# uc.net
KiCad netlist of a schematic drawn in Altium Designer
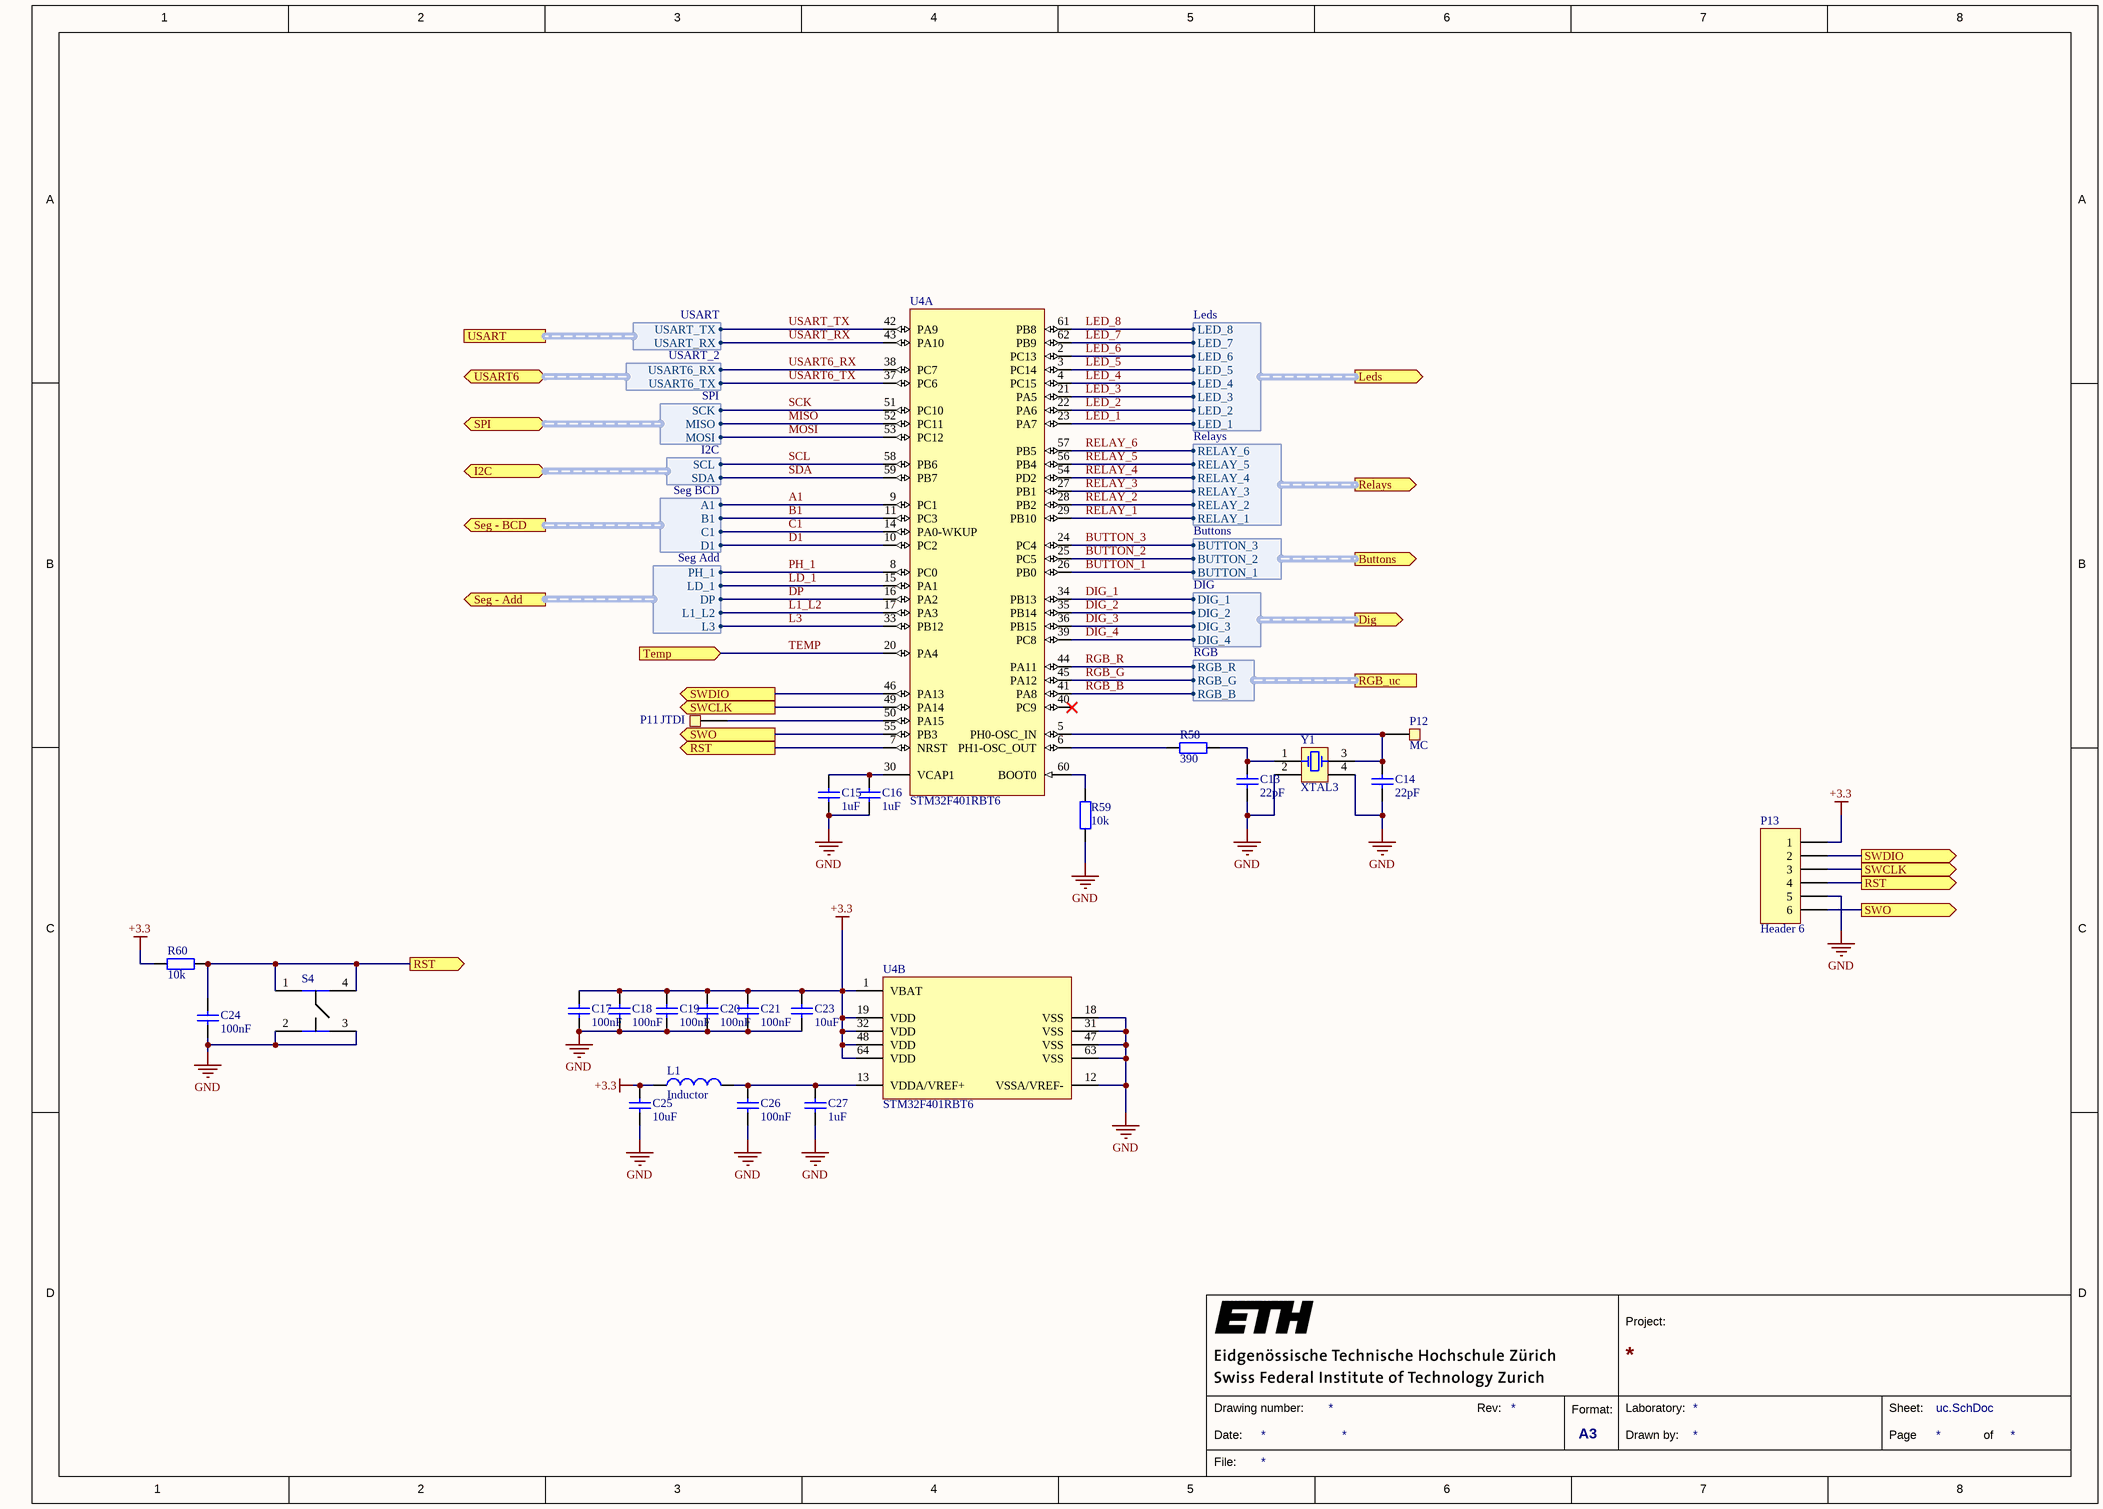
[diagram p0: uc.SchDoc]

(export (version "E")
  (design (tool "Eeschema 10.0.6"))
  (components
    (comp (ref "C13")
      (value "22pF")
      (footprint "CAP_0603i_1608m -N")
      (description "capacitor")
      (libsource (lib "IDSC std generic parts") (part "Cap"))
    )
    (comp (ref "C14")
      (value "22pF")
      (footprint "CAP_0603i_1608m -N")
      (description "capacitor")
      (libsource (lib "IDSC std generic parts") (part "Cap"))
    )
    (comp (ref "C15")
      (value "1uF")
      (footprint "CAP_0603i_1608m -N")
      (description "capacitor")
      (libsource (lib "IDSC std generic parts") (part "Cap"))
    )
    (comp (ref "C16")
      (value "1uF")
      (footprint "CAP_0603i_1608m -N")
      (description "capacitor")
      (libsource (lib "IDSC std generic parts") (part "Cap"))
    )
    (comp (ref "C17")
      (value "100nF")
      (footprint "CAP_0603i_1608m -N")
      (description "capacitor")
      (libsource (lib "IDSC std generic parts") (part "Cap"))
    )
    (comp (ref "C18")
      (value "100nF")
      (footprint "CAP_0603i_1608m -N")
      (description "capacitor")
      (libsource (lib "IDSC std generic parts") (part "Cap"))
    )
    (comp (ref "C19")
      (value "100nF")
      (footprint "CAP_0603i_1608m -N")
      (description "capacitor")
      (libsource (lib "IDSC std generic parts") (part "Cap"))
    )
    (comp (ref "C20")
      (value "100nF")
      (footprint "CAP_0603i_1608m -N")
      (description "capacitor")
      (libsource (lib "IDSC std generic parts") (part "Cap"))
    )
    (comp (ref "C21")
      (value "100nF")
      (footprint "CAP_0603i_1608m -N")
      (description "capacitor")
      (libsource (lib "IDSC std generic parts") (part "Cap"))
    )
    (comp (ref "C23")
      (value "10uF")
      (footprint "CAP_0805i_2012m -N")
      (description "capacitor")
      (libsource (lib "IDSC std generic parts") (part "Cap"))
    )
    (comp (ref "C24")
      (value "100nF")
      (footprint "CAP_0603i_1608m -N")
      (description "capacitor")
      (libsource (lib "IDSC std generic parts") (part "Cap"))
    )
    (comp (ref "C25")
      (value "10uF")
      (footprint "CAP_0805i_2012m -N")
      (description "capacitor")
      (libsource (lib "IDSC std generic parts") (part "Cap"))
    )
    (comp (ref "C26")
      (value "100nF")
      (footprint "CAP_0603i_1608m -N")
      (description "capacitor")
      (libsource (lib "IDSC std generic parts") (part "Cap"))
    )
    (comp (ref "C27")
      (value "1uF")
      (footprint "CAP_0603i_1608m -N")
      (description "capacitor")
      (libsource (lib "IDSC std generic parts") (part "Cap"))
    )
    (comp (ref "L1")
      (value "Inductor")
      (footprint "IND_0603i_1608m -L")
      (libsource (lib "IDSC std generic parts") (part "Inductor"))
    )
    (comp (ref "P11")
      (value "JTDI")
      (footprint "Pad_0603")
      (description "Single Pad or Testpoint")
      (libsource (lib "IDSC std connectors") (part "Pad"))
    )
    (comp (ref "P12")
      (value "MC")
      (footprint "Pad_3x3mm")
      (description "Single Pad or Testpoint")
      (libsource (lib "") (part "Pad_1"))
    )
    (comp (ref "P13")
      (value "Header 6")
      (footprint "HDR1X6")
      (description "Header, 6-Pin")
      (libsource (lib "IDSC std connectors") (part "Header 6"))
    )
    (comp (ref "R58")
      (value "390")
      (footprint "RES_0805i_2012m -N")
      (description "Resistor")
      (libsource (lib "") (part "Res_1"))
    )
    (comp (ref "R59")
      (value "10k")
      (footprint "RES_0603i_1608m -N")
      (description "Resistor")
      (libsource (lib "") (part "Res_1"))
    )
    (comp (ref "R60")
      (value "10k")
      (footprint "RES_0603i_1608m -N")
      (description "Resistor")
      (libsource (lib "IDSC std generic parts") (part "Res"))
    )
    (comp (ref "S4")
      (value "EVQ-Q2U02W")
      (footprint "EVQQ2")
      (description "White Button Tactile Switch, Single Pole Single Throw (SPST) 20 mA @ 15 V dc 0.7mm")
      (fields (field (name "MOUSER PART NUMBER") "667-EVQ-Q2U02W"))
      (libsource (lib "LIB") (part "EVQ-Q2U02W"))
    )
    (comp (ref "U4")
      (value "STM32F401RBT6")
      (footprint "STM-LQFP64_L")
      (fields (field (name "MANUFACTURER") "STMicroelectronics"))
      (libsource (lib "") (part "MC-ARM-STM32F401-SQ64_1"))
    )
    (comp (ref "Y1")
      (value "XTAL3")
      (footprint "TSX-3225 2*2.5")
      (description "Industrial Ceramic Resonator")
      (libsource (lib "IDSC std generic parts") (part "XTAL3"))
    )
  )
  (nets
    (net (code "13") (name "+3.3") (class "Default")
      (node (ref "C17") (pin "1") (pinfunction "1_1") (pintype "passive"))
      (node (ref "C18") (pin "2") (pinfunction "2_2") (pintype "passive"))
      (node (ref "C19") (pin "2") (pinfunction "2_2") (pintype "passive"))
      (node (ref "C20") (pin "1") (pinfunction "1_1") (pintype "passive"))
      (node (ref "C21") (pin "2") (pinfunction "2_2") (pintype "passive"))
      (node (ref "C23") (pin "2") (pinfunction "2_2") (pintype "passive"))
      (node (ref "C25") (pin "2") (pinfunction "2_2") (pintype "passive"))
      (node (ref "L1") (pin "2") (pinfunction "2_2") (pintype "passive"))
      (node (ref "P13") (pin "1") (pinfunction "1_1") (pintype "passive"))
      (node (ref "R60") (pin "1") (pinfunction "1_1") (pintype "passive"))
      (node (ref "U4") (pin "1") (pinfunction "VBAT_1") (pintype "power_in"))
      (node (ref "U4") (pin "19") (pinfunction "VDD_19") (pintype "power_in"))
      (node (ref "U4") (pin "32") (pinfunction "VDD_32") (pintype "power_in"))
      (node (ref "U4") (pin "48") (pinfunction "VDD_48") (pintype "power_in"))
      (node (ref "U4") (pin "64") (pinfunction "VDD_64") (pintype "power_in"))
    )
    (net (code "14") (name "/A1") (class "Default")
      (node (ref "U4") (pin "9") (pinfunction "PC1_9") (pintype "bidirectional"))
    )
    (net (code "15") (name "/B1") (class "Default")
      (node (ref "U4") (pin "11") (pinfunction "PC3_11") (pintype "bidirectional"))
    )
    (net (code "16") (name "/BUTTON_1") (class "Default")
      (node (ref "U4") (pin "26") (pinfunction "PB0_26") (pintype "bidirectional"))
    )
    (net (code "17") (name "/BUTTON_2") (class "Default")
      (node (ref "U4") (pin "25") (pinfunction "PC5_25") (pintype "bidirectional"))
    )
    (net (code "18") (name "/BUTTON_3") (class "Default")
      (node (ref "U4") (pin "24") (pinfunction "PC4_24") (pintype "bidirectional"))
    )
    (net (code "19") (name "/C1") (class "Default")
      (node (ref "U4") (pin "14") (pinfunction "PA0-WKUP_14") (pintype "bidirectional"))
    )
    (net (code "20") (name "/D1") (class "Default")
      (node (ref "U4") (pin "10") (pinfunction "PC2_10") (pintype "bidirectional"))
    )
    (net (code "21") (name "/DIG_1") (class "Default")
      (node (ref "U4") (pin "34") (pinfunction "PB13_34") (pintype "bidirectional"))
    )
    (net (code "22") (name "/DIG_2") (class "Default")
      (node (ref "U4") (pin "35") (pinfunction "PB14_35") (pintype "bidirectional"))
    )
    (net (code "23") (name "/DIG_3") (class "Default")
      (node (ref "U4") (pin "36") (pinfunction "PB15_36") (pintype "bidirectional"))
    )
    (net (code "24") (name "/DIG_4") (class "Default")
      (node (ref "U4") (pin "39") (pinfunction "PC8_39") (pintype "bidirectional"))
    )
    (net (code "25") (name "/DP") (class "Default")
      (node (ref "U4") (pin "16") (pinfunction "PA2_16") (pintype "bidirectional"))
    )
    (net (code "26") (name "/L1_L2") (class "Default")
      (node (ref "U4") (pin "17") (pinfunction "PA3_17") (pintype "bidirectional"))
    )
    (net (code "27") (name "/L3") (class "Default")
      (node (ref "U4") (pin "33") (pinfunction "PB12_33") (pintype "bidirectional"))
    )
    (net (code "28") (name "/LD_1") (class "Default")
      (node (ref "U4") (pin "15") (pinfunction "PA1_15") (pintype "bidirectional"))
    )
    (net (code "29") (name "/LED_1") (class "Default")
      (node (ref "U4") (pin "23") (pinfunction "PA7_23") (pintype "bidirectional"))
    )
    (net (code "30") (name "/LED_2") (class "Default")
      (node (ref "U4") (pin "22") (pinfunction "PA6_22") (pintype "bidirectional"))
    )
    (net (code "31") (name "/LED_3") (class "Default")
      (node (ref "U4") (pin "21") (pinfunction "PA5_21") (pintype "bidirectional"))
    )
    (net (code "32") (name "/LED_4") (class "Default")
      (node (ref "U4") (pin "4") (pinfunction "PC15_4") (pintype "bidirectional"))
    )
    (net (code "33") (name "/LED_5") (class "Default")
      (node (ref "U4") (pin "3") (pinfunction "PC14_3") (pintype "bidirectional"))
    )
    (net (code "34") (name "/LED_6") (class "Default")
      (node (ref "U4") (pin "2") (pinfunction "PC13_2") (pintype "bidirectional"))
    )
    (net (code "35") (name "/LED_7") (class "Default")
      (node (ref "U4") (pin "62") (pinfunction "PB9_62") (pintype "bidirectional"))
    )
    (net (code "36") (name "/LED_8") (class "Default")
      (node (ref "U4") (pin "61") (pinfunction "PB8_61") (pintype "bidirectional"))
    )
    (net (code "37") (name "/MISO") (class "Default")
      (node (ref "U4") (pin "52") (pinfunction "PC11_52") (pintype "bidirectional"))
    )
    (net (code "38") (name "/MOSI") (class "Default")
      (node (ref "U4") (pin "53") (pinfunction "PC12_53") (pintype "bidirectional"))
    )
    (net (code "39") (name "/PH_1") (class "Default")
      (node (ref "U4") (pin "8") (pinfunction "PC0_8") (pintype "bidirectional"))
    )
    (net (code "40") (name "/RELAY_1") (class "Default")
      (node (ref "U4") (pin "29") (pinfunction "PB10_29") (pintype "bidirectional"))
    )
    (net (code "41") (name "/RELAY_2") (class "Default")
      (node (ref "U4") (pin "28") (pinfunction "PB2_28") (pintype "bidirectional"))
    )
    (net (code "42") (name "/RELAY_3") (class "Default")
      (node (ref "U4") (pin "27") (pinfunction "PB1_27") (pintype "bidirectional"))
    )
    (net (code "43") (name "/RELAY_4") (class "Default")
      (node (ref "U4") (pin "54") (pinfunction "PD2_54") (pintype "bidirectional"))
    )
    (net (code "44") (name "/RELAY_5") (class "Default")
      (node (ref "U4") (pin "56") (pinfunction "PB4_56") (pintype "bidirectional"))
    )
    (net (code "45") (name "/RELAY_6") (class "Default")
      (node (ref "U4") (pin "57") (pinfunction "PB5_57") (pintype "bidirectional"))
    )
    (net (code "46") (name "/RGB_B") (class "Default")
      (node (ref "U4") (pin "41") (pinfunction "PA8_41") (pintype "bidirectional"))
    )
    (net (code "47") (name "/RGB_G") (class "Default")
      (node (ref "U4") (pin "45") (pinfunction "PA12_45") (pintype "bidirectional"))
    )
    (net (code "48") (name "/RGB_R") (class "Default")
      (node (ref "U4") (pin "44") (pinfunction "PA11_44") (pintype "bidirectional"))
    )
    (net (code "49") (name "/RST") (class "Default")
      (node (ref "C24") (pin "2") (pinfunction "2_2") (pintype "passive"))
      (node (ref "P13") (pin "4") (pinfunction "4_4") (pintype "passive"))
      (node (ref "R60") (pin "2") (pinfunction "2_2") (pintype "passive"))
      (node (ref "S4") (pin "1") (pinfunction "NO_1_1") (pintype "passive"))
      (node (ref "S4") (pin "4") (pinfunction "NO_2_4") (pintype "passive"))
      (node (ref "U4") (pin "7") (pinfunction "NRST_7") (pintype "bidirectional"))
    )
    (net (code "50") (name "/SCK") (class "Default")
      (node (ref "U4") (pin "51") (pinfunction "PC10_51") (pintype "bidirectional"))
    )
    (net (code "51") (name "/SCL") (class "Default")
      (node (ref "U4") (pin "58") (pinfunction "PB6_58") (pintype "bidirectional"))
    )
    (net (code "52") (name "/SDA") (class "Default")
      (node (ref "U4") (pin "59") (pinfunction "PB7_59") (pintype "bidirectional"))
    )
    (net (code "53") (name "/SWCLK") (class "Default")
      (node (ref "P13") (pin "3") (pinfunction "3_3") (pintype "passive"))
      (node (ref "U4") (pin "49") (pinfunction "PA14_49") (pintype "bidirectional"))
    )
    (net (code "54") (name "/SWDIO") (class "Default")
      (node (ref "P13") (pin "2") (pinfunction "2_2") (pintype "passive"))
      (node (ref "U4") (pin "46") (pinfunction "PA13_46") (pintype "bidirectional"))
    )
    (net (code "55") (name "/SWO") (class "Default")
      (node (ref "P13") (pin "6") (pinfunction "6_6") (pintype "passive"))
      (node (ref "U4") (pin "55") (pinfunction "PB3_55") (pintype "bidirectional"))
    )
    (net (code "56") (name "/TEMP") (class "Default")
      (node (ref "U4") (pin "20") (pinfunction "PA4_20") (pintype "bidirectional"))
    )
    (net (code "57") (name "/USART6_RX") (class "Default")
      (node (ref "U4") (pin "38") (pinfunction "PC7_38") (pintype "bidirectional"))
    )
    (net (code "58") (name "/USART6_TX") (class "Default")
      (node (ref "U4") (pin "37") (pinfunction "PC6_37") (pintype "bidirectional"))
    )
    (net (code "59") (name "/USART_RX") (class "Default")
      (node (ref "U4") (pin "43") (pinfunction "PA10_43") (pintype "bidirectional"))
    )
    (net (code "60") (name "/USART_TX") (class "Default")
      (node (ref "U4") (pin "42") (pinfunction "PA9_42") (pintype "bidirectional"))
    )
    (net (code "72") (name "GND") (class "Default")
      (node (ref "C13") (pin "1") (pinfunction "1_1") (pintype "passive"))
      (node (ref "C14") (pin "1") (pinfunction "1_1") (pintype "passive"))
      (node (ref "C15") (pin "1") (pinfunction "1_1") (pintype "passive"))
      (node (ref "C16") (pin "1") (pinfunction "1_1") (pintype "passive"))
      (node (ref "C17") (pin "2") (pinfunction "2_2") (pintype "passive"))
      (node (ref "C18") (pin "1") (pinfunction "1_1") (pintype "passive"))
      (node (ref "C19") (pin "1") (pinfunction "1_1") (pintype "passive"))
      (node (ref "C20") (pin "2") (pinfunction "2_2") (pintype "passive"))
      (node (ref "C21") (pin "1") (pinfunction "1_1") (pintype "passive"))
      (node (ref "C23") (pin "1") (pinfunction "1_1") (pintype "passive"))
      (node (ref "C24") (pin "1") (pinfunction "1_1") (pintype "passive"))
      (node (ref "C25") (pin "1") (pinfunction "1_1") (pintype "passive"))
      (node (ref "C26") (pin "1") (pinfunction "1_1") (pintype "passive"))
      (node (ref "C27") (pin "1") (pinfunction "1_1") (pintype "passive"))
      (node (ref "P13") (pin "5") (pinfunction "5_5") (pintype "passive"))
      (node (ref "R59") (pin "1") (pinfunction "1_1") (pintype "passive"))
      (node (ref "S4") (pin "2") (pinfunction "COM_1_2") (pintype "passive"))
      (node (ref "S4") (pin "3") (pinfunction "COM_2_3") (pintype "passive"))
      (node (ref "U4") (pin "12") (pinfunction "VSSA/VREF-_12") (pintype "power_in"))
      (node (ref "U4") (pin "18") (pinfunction "VSS_18") (pintype "power_in"))
      (node (ref "U4") (pin "31") (pinfunction "VSS_31") (pintype "power_in"))
      (node (ref "U4") (pin "47") (pinfunction "VSS_47") (pintype "power_in"))
      (node (ref "U4") (pin "63") (pinfunction "VSS_63") (pintype "power_in"))
      (node (ref "Y1") (pin "2") (pinfunction "COM_2") (pintype "passive"))
      (node (ref "Y1") (pin "4") (pinfunction "COM_4") (pintype "passive"))
    )
    (net (code "73") (name "Net-(U4A-BOOT0)") (class "Default")
      (node (ref "R59") (pin "2") (pinfunction "2_2") (pintype "passive"))
      (node (ref "U4") (pin "60") (pinfunction "BOOT0_60") (pintype "input"))
    )
    (net (code "74") (name "Net-(U4A-PA15)") (class "Default")
      (node (ref "P11") (pin "1") (pinfunction "1_1") (pintype "passive"))
      (node (ref "U4") (pin "50") (pinfunction "PA15_50") (pintype "bidirectional"))
    )
    (net (code "75") (name "Net-(U4A-PH0-OSC_IN)") (class "Default")
      (node (ref "C14") (pin "2") (pinfunction "2_2") (pintype "passive"))
      (node (ref "P12") (pin "1") (pinfunction "1_1") (pintype "passive"))
      (node (ref "U4") (pin "5") (pinfunction "PH0-OSC_IN_5") (pintype "bidirectional"))
      (node (ref "Y1") (pin "3") (pinfunction "OSC2_3") (pintype "passive"))
    )
    (net (code "76") (name "Net-(U4A-PH1-OSC_OUT)") (class "Default")
      (node (ref "R58") (pin "1") (pinfunction "1_1") (pintype "passive"))
      (node (ref "U4") (pin "6") (pinfunction "PH1-OSC_OUT_6") (pintype "bidirectional"))
    )
    (net (code "77") (name "Net-(U4A-VCAP1)") (class "Default")
      (node (ref "C15") (pin "2") (pinfunction "2_2") (pintype "passive"))
      (node (ref "C16") (pin "2") (pinfunction "2_2") (pintype "passive"))
      (node (ref "U4") (pin "30") (pinfunction "VCAP1_30") (pintype "power_in"))
    )
    (net (code "78") (name "Net-(U4B-VDDA{slash}VREF+)") (class "Default")
      (node (ref "C26") (pin "2") (pinfunction "2_2") (pintype "passive"))
      (node (ref "C27") (pin "2") (pinfunction "2_2") (pintype "passive"))
      (node (ref "L1") (pin "1") (pinfunction "1_1") (pintype "passive"))
      (node (ref "U4") (pin "13") (pinfunction "VDDA/VREF+_13") (pintype "power_in"))
    )
    (net (code "79") (name "Net-(Y1-OSC1)") (class "Default")
      (node (ref "C13") (pin "2") (pinfunction "2_2") (pintype "passive"))
      (node (ref "R58") (pin "2") (pinfunction "2_2") (pintype "passive"))
      (node (ref "Y1") (pin "1") (pinfunction "OSC1_1") (pintype "passive"))
    )
    (net (code "80") (name "unconnected-(U4A-PC9-Pad40)") (class "Default")
      (node (ref "U4") (pin "40") (pinfunction "PC9_40") (pintype "bidirectional+no_connect"))
    )
  )
)
